# uNav44_r1.net
KiCad netlist of a schematic drawn in EAGLE
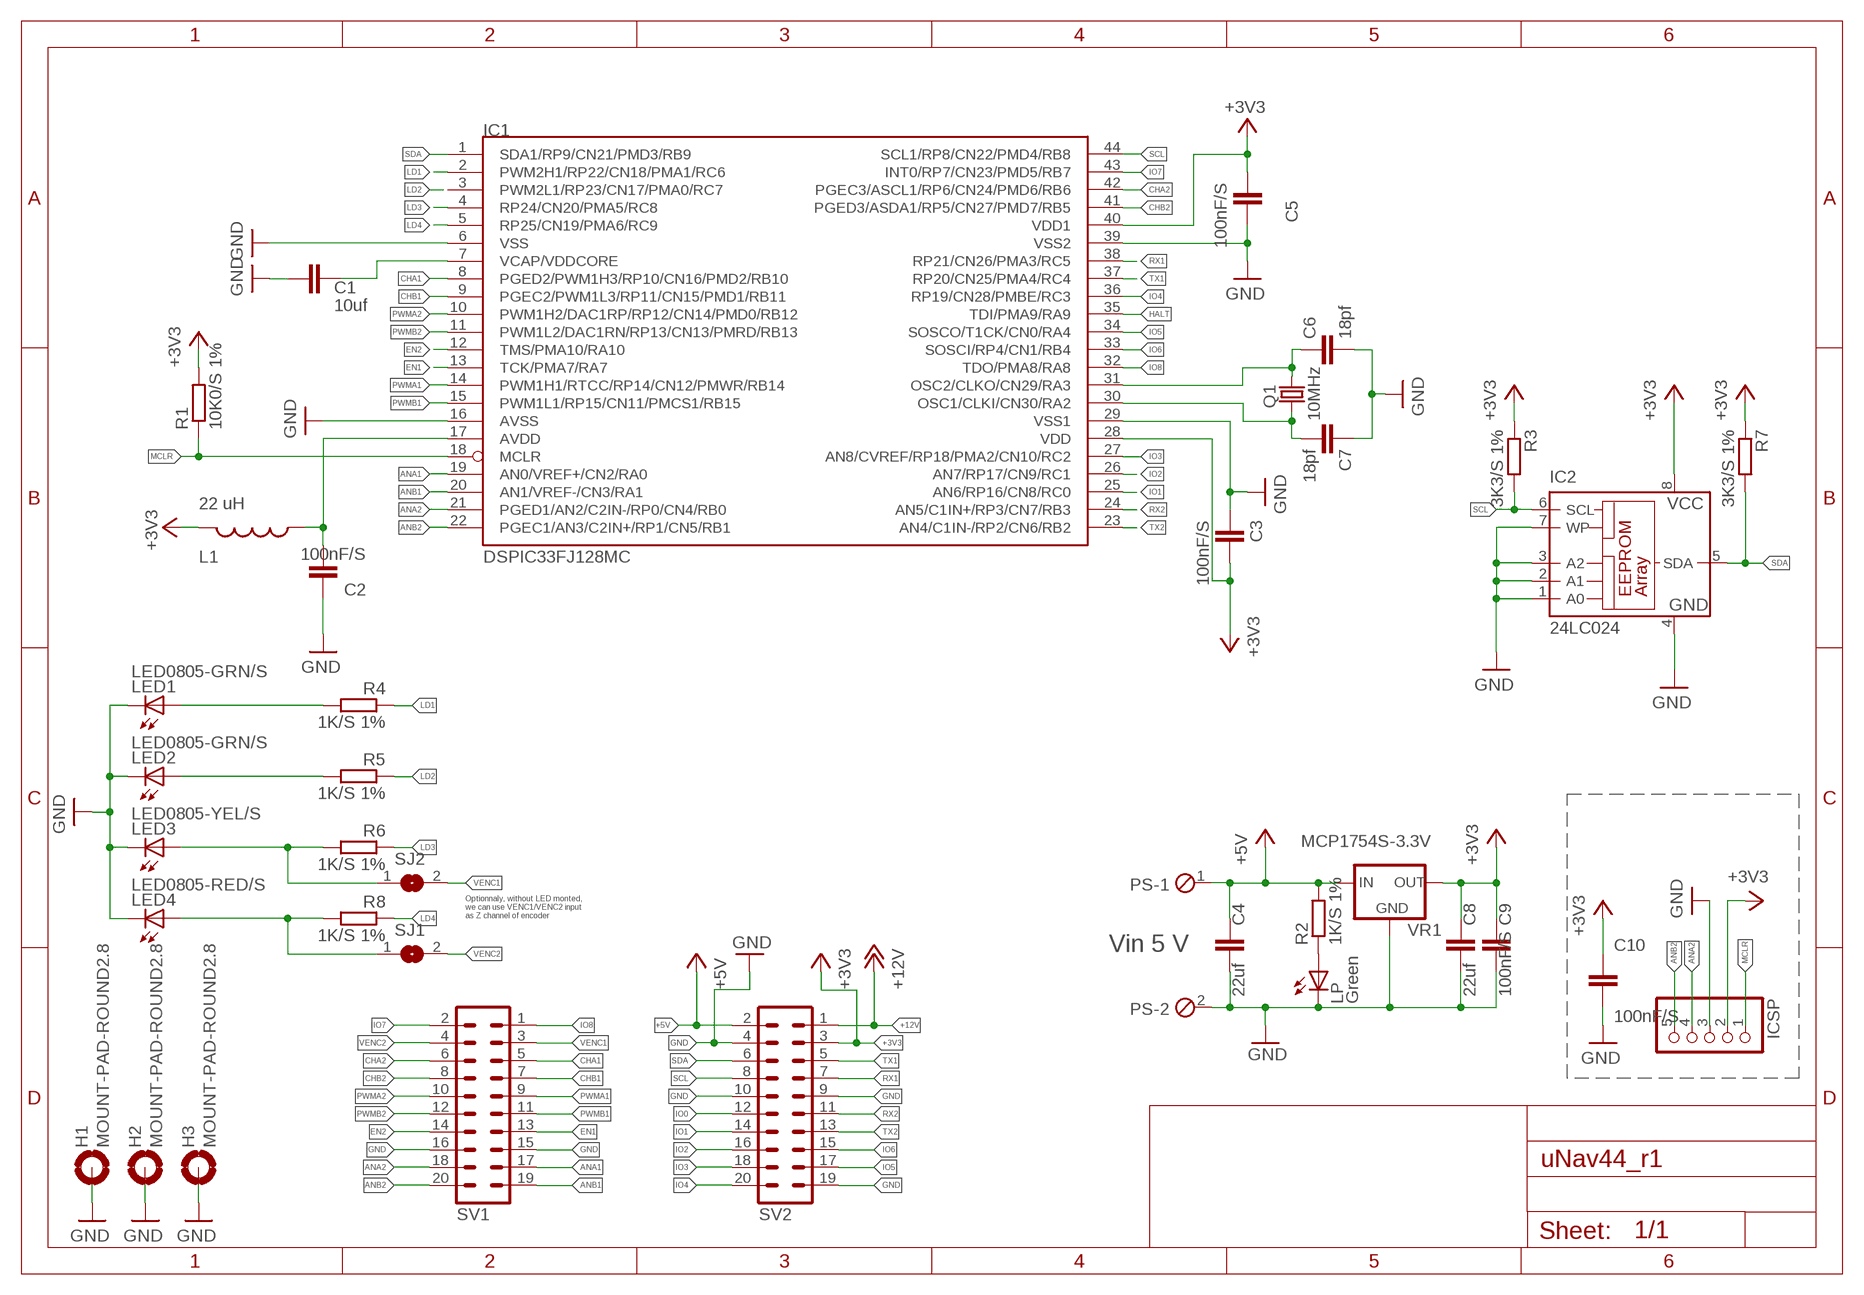
[diagram p0: schematic, sheet 1]

(export (version "E")
  (design (tool "Eeschema 10.0.6"))
  (components
    (comp (ref "C1")
      (value "10uf")
      (footprint "eagle-import:C1206")
      (libsource (lib "eagle-import") (part "C-EUC1206"))
    )
    (comp (ref "C2")
      (value "100nF/S")
      (footprint "eagle-import:C0603")
      (libsource (lib "eagle-import") (part "C-EUC0603"))
    )
    (comp (ref "C3")
      (value "100nF/S")
      (footprint "eagle-import:C0603")
      (libsource (lib "eagle-import") (part "C-EUC0603"))
    )
    (comp (ref "C4")
      (value "22uf")
      (footprint "eagle-import:C1206")
      (libsource (lib "eagle-import") (part "C-EUC1206"))
    )
    (comp (ref "C5")
      (value "100nF/S")
      (footprint "eagle-import:C0603")
      (libsource (lib "eagle-import") (part "C-EUC0603"))
    )
    (comp (ref "C6")
      (value "18pf")
      (footprint "eagle-import:C0603")
      (libsource (lib "eagle-import") (part "C-EUC0603"))
    )
    (comp (ref "C7")
      (value "18pf")
      (footprint "eagle-import:C0603")
      (libsource (lib "eagle-import") (part "C-EUC0603"))
    )
    (comp (ref "C8")
      (value "22uf")
      (footprint "eagle-import:C1206")
      (libsource (lib "eagle-import") (part "C-EUC1206"))
    )
    (comp (ref "C9")
      (value "100nF/S")
      (footprint "eagle-import:C0603")
      (libsource (lib "eagle-import") (part "C-EUC0603"))
    )
    (comp (ref "C10")
      (value "100nF/S")
      (footprint "eagle-import:C0603")
      (libsource (lib "eagle-import") (part "C-EUC0603"))
    )
    (comp (ref "H1")
      (value "MOUNT-PAD-ROUND2.8")
      (footprint "eagle-import:2,8-PAD")
      (libsource (lib "eagle-import") (part "MOUNT-PAD-ROUND2.8"))
    )
    (comp (ref "H2")
      (value "MOUNT-PAD-ROUND2.8")
      (footprint "eagle-import:2,8-PAD")
      (libsource (lib "eagle-import") (part "MOUNT-PAD-ROUND2.8"))
    )
    (comp (ref "H3")
      (value "MOUNT-PAD-ROUND2.8")
      (footprint "eagle-import:2,8-PAD")
      (libsource (lib "eagle-import") (part "MOUNT-PAD-ROUND2.8"))
    )
    (comp (ref "IC1")
      (value "DSPIC33FJ128MC")
      (footprint "eagle-import:TQFP44")
      (libsource (lib "eagle-import") (part "DSPIC33FJ128MC804-PT"))
    )
    (comp (ref "IC2")
      (value "24LC024")
      (footprint "eagle-import:SO-08M")
      (fields (field (name "MF") "MICROCHIP") (field (name "MPN") "24AA01-I/SN"))
      (libsource (lib "eagle-import") (part "24SMAA01"))
    )
    (comp (ref "ICSP")
      (value "PINHD-1X05_2.54-S")
      (footprint "eagle-import:1X05-S")
      (libsource (lib "eagle-import") (part "PINHD-1X05_2.54-S"))
    )
    (comp (ref "L1")
      (value "22 uH")
      (footprint "eagle-import:0805")
      (libsource (lib "eagle-import") (part "INDUCTOR0805"))
    )
    (comp (ref "LED1")
      (value "LED0805-GRN/S")
      (footprint "eagle-import:CHIPLED_0805")
      (libsource (lib "eagle-import") (part "LEDCHIPLED_0805"))
    )
    (comp (ref "LED2")
      (value "LED0805-GRN/S")
      (footprint "eagle-import:CHIPLED_0805")
      (libsource (lib "eagle-import") (part "LEDCHIPLED_0805"))
    )
    (comp (ref "LED3")
      (value "LED0805-YEL/S")
      (footprint "eagle-import:CHIPLED_0805")
      (libsource (lib "eagle-import") (part "LEDCHIPLED_0805"))
    )
    (comp (ref "LED4")
      (value "LED0805-RED/S")
      (footprint "eagle-import:CHIPLED_0805")
      (libsource (lib "eagle-import") (part "LEDCHIPLED_0805"))
    )
    (comp (ref "LP")
      (value "Green")
      (footprint "eagle-import:CHIPLED_0805")
      (libsource (lib "eagle-import") (part "LEDCHIPLED_0805"))
    )
    (comp (ref "PS")
      (value "MPT2")
      (footprint "eagle-import:2POL254")
      (libsource (lib "eagle-import") (part "MPT2"))
    )
    (comp (ref "Q1")
      (value "10MHz")
      (footprint "eagle-import:HC49U-V")
      (libsource (lib "eagle-import") (part "CRYSTALHC49U-V"))
    )
    (comp (ref "R1")
      (value "10K0/S 1%")
      (footprint "eagle-import:R0603")
      (libsource (lib "eagle-import") (part "R-EU_R0603"))
    )
    (comp (ref "R2")
      (value "1K/S 1%")
      (footprint "eagle-import:R0603")
      (libsource (lib "eagle-import") (part "R-EU_R0603"))
    )
    (comp (ref "R3")
      (value "3K3/S 1%")
      (footprint "eagle-import:R0603")
      (libsource (lib "eagle-import") (part "R-EU_R0603"))
    )
    (comp (ref "R4")
      (value "1K/S 1%")
      (footprint "eagle-import:R0603")
      (libsource (lib "eagle-import") (part "R-EU_R0603"))
    )
    (comp (ref "R5")
      (value "1K/S 1%")
      (footprint "eagle-import:R0603")
      (libsource (lib "eagle-import") (part "R-EU_R0603"))
    )
    (comp (ref "R6")
      (value "1K/S 1%")
      (footprint "eagle-import:R0603")
      (libsource (lib "eagle-import") (part "R-EU_R0603"))
    )
    (comp (ref "R7")
      (value "3K3/S 1%")
      (footprint "eagle-import:R0603")
      (libsource (lib "eagle-import") (part "R-EU_R0603"))
    )
    (comp (ref "R8")
      (value "1K/S 1%")
      (footprint "eagle-import:R0603")
      (libsource (lib "eagle-import") (part "R-EU_R0603"))
    )
    (comp (ref "SJ1") (value "SJ") (footprint "eagle-import:SJ") (libsource (lib "eagle-import") (part "SJ")))
    (comp (ref "SJ2") (value "SJ") (footprint "eagle-import:SJ") (libsource (lib "eagle-import") (part "SJ")))
    (comp (ref "SV1")
      (value "MA10-2")
      (footprint "eagle-import:MA10-2")
      (fields (field (name "OC_FARNELL") "unknown") (field (name "OC_NEWARK") "unknown"))
      (libsource (lib "eagle-import") (part "MA10-2"))
    )
    (comp (ref "SV2")
      (value "MA10-2")
      (footprint "eagle-import:MA10-2")
      (libsource (lib "eagle-import") (part "MA10-2"))
    )
    (comp (ref "VR1")
      (value "MCP1754S-3.3V")
      (footprint "eagle-import:SOT89")
      (libsource (lib "eagle-import") (part "MCP1754S"))
    )
  )
  (nets
    (net (code "1") (name "+3V3") (class "Default")
      (node (ref "C10") (pin "1") (pinfunction "1_1") (pintype "passive"))
      (node (ref "C3") (pin "1") (pinfunction "1_1") (pintype "passive"))
      (node (ref "C5") (pin "2") (pinfunction "2_2") (pintype "passive"))
      (node (ref "C8") (pin "1") (pinfunction "1_1") (pintype "passive"))
      (node (ref "C9") (pin "1") (pinfunction "1_1") (pintype "passive"))
      (node (ref "IC1") (pin "28") (pinfunction "VDD_28") (pintype "power_in"))
      (node (ref "IC1") (pin "40") (pinfunction "VDD1_40") (pintype "power_in"))
      (node (ref "IC2") (pin "8") (pinfunction "VCC_8") (pintype "power_in"))
      (node (ref "ICSP") (pin "2") (pinfunction "2_2") (pintype "passive"))
      (node (ref "L1") (pin "2") (pinfunction "2_2") (pintype "passive"))
      (node (ref "R1") (pin "2") (pinfunction "2_2") (pintype "passive"))
      (node (ref "R3") (pin "1") (pinfunction "1_1") (pintype "passive"))
      (node (ref "R7") (pin "1") (pinfunction "1_1") (pintype "passive"))
      (node (ref "SV2") (pin "3") (pinfunction "3_3") (pintype "passive"))
      (node (ref "VR1") (pin "3") (pinfunction "OUT_3") (pintype "passive"))
    )
    (net (code "2") (name "+5V") (class "Default")
      (node (ref "C4") (pin "1") (pinfunction "1_1") (pintype "passive"))
      (node (ref "PS") (pin "1") (pinfunction "1_1") (pintype "passive"))
      (node (ref "R2") (pin "2") (pinfunction "2_2") (pintype "passive"))
      (node (ref "SV2") (pin "2") (pinfunction "2_2") (pintype "passive"))
      (node (ref "VR1") (pin "1") (pinfunction "IN_1") (pintype "input"))
    )
    (net (code "3") (name "+12V") (class "Default")
      (node (ref "SV2") (pin "1") (pinfunction "1_1") (pintype "passive"))
    )
    (net (code "4") (name "ANA1") (class "Default")
      (node (ref "IC1") (pin "19") (pinfunction "AN0/VREF+/CN2/RA0_19") (pintype "bidirectional"))
      (node (ref "SV1") (pin "17") (pinfunction "17_17") (pintype "passive"))
    )
    (net (code "5") (name "ANA2") (class "Default")
      (node (ref "IC1") (pin "21") (pinfunction "PGED1/AN2/C2IN-/RP0/CN4/RB0_21") (pintype "bidirectional"))
      (node (ref "ICSP") (pin "4") (pinfunction "4_4") (pintype "passive"))
      (node (ref "SV1") (pin "18") (pinfunction "18_18") (pintype "passive"))
    )
    (net (code "6") (name "ANB1") (class "Default")
      (node (ref "IC1") (pin "20") (pinfunction "AN1/VREF-/CN3/RA1_20") (pintype "bidirectional"))
      (node (ref "SV1") (pin "19") (pinfunction "19_19") (pintype "passive"))
    )
    (net (code "7") (name "ANB2") (class "Default")
      (node (ref "IC1") (pin "22") (pinfunction "PGEC1/AN3/C2IN+/RP1/CN5/RB1_22") (pintype "bidirectional"))
      (node (ref "ICSP") (pin "5") (pinfunction "5_5") (pintype "passive"))
      (node (ref "SV1") (pin "20") (pinfunction "20_20") (pintype "passive"))
    )
    (net (code "8") (name "CHA1") (class "Default")
      (node (ref "IC1") (pin "8") (pinfunction "PGED2/PWM1H3/RP10/CN16/PMD2/RB10_8") (pintype "bidirectional"))
      (node (ref "SV1") (pin "5") (pinfunction "5_5") (pintype "passive"))
    )
    (net (code "9") (name "CHA2") (class "Default")
      (node (ref "IC1") (pin "42") (pinfunction "PGEC3/ASCL1/RP6/CN24/PMD6/RB6_42") (pintype "bidirectional"))
      (node (ref "SV1") (pin "6") (pinfunction "6_6") (pintype "passive"))
    )
    (net (code "10") (name "CHB1") (class "Default")
      (node (ref "IC1") (pin "9") (pinfunction "PGEC2/PWM1L3/RP11/CN15/PMD1/RB11_9") (pintype "bidirectional"))
      (node (ref "SV1") (pin "7") (pinfunction "7_7") (pintype "passive"))
    )
    (net (code "11") (name "CHB2") (class "Default")
      (node (ref "IC1") (pin "41") (pinfunction "PGED3/ASDA1/RP5/CN27/PMD7/RB5_41") (pintype "bidirectional"))
      (node (ref "SV1") (pin "8") (pinfunction "8_8") (pintype "passive"))
    )
    (net (code "12") (name "EN1") (class "Default")
      (node (ref "IC1") (pin "13") (pinfunction "TCK/PMA7/RA7_13") (pintype "bidirectional"))
      (node (ref "SV1") (pin "13") (pinfunction "13_13") (pintype "passive"))
    )
    (net (code "13") (name "EN2") (class "Default")
      (node (ref "IC1") (pin "12") (pinfunction "TMS/PMA10/RA10_12") (pintype "bidirectional"))
      (node (ref "SV1") (pin "14") (pinfunction "14_14") (pintype "passive"))
    )
    (net (code "14") (name "GND") (class "Default")
      (node (ref "C1") (pin "2") (pinfunction "2_2") (pintype "passive"))
      (node (ref "C10") (pin "2") (pinfunction "2_2") (pintype "passive"))
      (node (ref "C2") (pin "1") (pinfunction "1_1") (pintype "passive"))
      (node (ref "C3") (pin "2") (pinfunction "2_2") (pintype "passive"))
      (node (ref "C4") (pin "2") (pinfunction "2_2") (pintype "passive"))
      (node (ref "C5") (pin "1") (pinfunction "1_1") (pintype "passive"))
      (node (ref "C6") (pin "2") (pinfunction "2_2") (pintype "passive"))
      (node (ref "C7") (pin "1") (pinfunction "1_1") (pintype "passive"))
      (node (ref "C8") (pin "2") (pinfunction "2_2") (pintype "passive"))
      (node (ref "C9") (pin "2") (pinfunction "2_2") (pintype "passive"))
      (node (ref "H1") (pin "B2,8") (pinfunction "MOUNT_B2,8") (pintype "passive"))
      (node (ref "H2") (pin "B2,8") (pinfunction "MOUNT_B2,8") (pintype "passive"))
      (node (ref "H3") (pin "B2,8") (pinfunction "MOUNT_B2,8") (pintype "passive"))
      (node (ref "IC1") (pin "16") (pinfunction "AVSS_16") (pintype "power_in"))
      (node (ref "IC1") (pin "29") (pinfunction "VSS1_29") (pintype "power_in"))
      (node (ref "IC1") (pin "39") (pinfunction "VSS2_39") (pintype "power_in"))
      (node (ref "IC1") (pin "6") (pinfunction "VSS_6") (pintype "power_in"))
      (node (ref "IC2") (pin "1") (pinfunction "A0_1") (pintype "input"))
      (node (ref "IC2") (pin "2") (pinfunction "A1_2") (pintype "input"))
      (node (ref "IC2") (pin "3") (pinfunction "A2_3") (pintype "input"))
      (node (ref "IC2") (pin "4") (pinfunction "GND_4") (pintype "power_in"))
      (node (ref "IC2") (pin "7") (pinfunction "WP_7") (pintype "input"))
      (node (ref "ICSP") (pin "3") (pinfunction "3_3") (pintype "passive"))
      (node (ref "LED1") (pin "C") (pinfunction "C_C") (pintype "passive"))
      (node (ref "LED2") (pin "C") (pinfunction "C_C") (pintype "passive"))
      (node (ref "LED3") (pin "C") (pinfunction "C_C") (pintype "passive"))
      (node (ref "LED4") (pin "C") (pinfunction "C_C") (pintype "passive"))
      (node (ref "LP") (pin "C") (pinfunction "C_C") (pintype "passive"))
      (node (ref "PS") (pin "2") (pinfunction "1_2") (pintype "passive"))
      (node (ref "SV1") (pin "15") (pinfunction "15_15") (pintype "passive"))
      (node (ref "SV1") (pin "16") (pinfunction "16_16") (pintype "passive"))
      (node (ref "SV2") (pin "10") (pinfunction "10_10") (pintype "passive"))
      (node (ref "SV2") (pin "19") (pinfunction "19_19") (pintype "passive"))
      (node (ref "SV2") (pin "4") (pinfunction "4_4") (pintype "passive"))
      (node (ref "SV2") (pin "9") (pinfunction "9_9") (pintype "passive"))
      (node (ref "VR1") (pin "2") (pinfunction "GND_2") (pintype "input"))
      (node (ref "VR1") (pin "4") (pinfunction "GND_4") (pintype "input"))
    )
    (net (code "15") (name "HALT") (class "Default")
      (node (ref "IC1") (pin "35") (pinfunction "TDI/PMA9/RA9_35") (pintype "bidirectional"))
    )
    (net (code "16") (name "IO0") (class "Default")
      (node (ref "SV2") (pin "12") (pinfunction "12_12") (pintype "passive"))
    )
    (net (code "17") (name "IO1") (class "Default")
      (node (ref "IC1") (pin "25") (pinfunction "AN6/RP16/CN8/RC0_25") (pintype "bidirectional"))
      (node (ref "SV2") (pin "14") (pinfunction "14_14") (pintype "passive"))
    )
    (net (code "18") (name "IO2") (class "Default")
      (node (ref "IC1") (pin "26") (pinfunction "AN7/RP17/CN9/RC1_26") (pintype "bidirectional"))
      (node (ref "SV2") (pin "16") (pinfunction "16_16") (pintype "passive"))
    )
    (net (code "19") (name "IO3") (class "Default")
      (node (ref "IC1") (pin "27") (pinfunction "AN8/CVREF/RP18/PMA2/CN10/RC2_27") (pintype "bidirectional"))
      (node (ref "SV2") (pin "18") (pinfunction "18_18") (pintype "passive"))
    )
    (net (code "20") (name "IO4") (class "Default")
      (node (ref "IC1") (pin "36") (pinfunction "RP19/CN28/PMBE/RC3_36") (pintype "bidirectional"))
      (node (ref "SV2") (pin "20") (pinfunction "20_20") (pintype "passive"))
    )
    (net (code "21") (name "IO5") (class "Default")
      (node (ref "IC1") (pin "34") (pinfunction "SOSCO/T1CK/CN0/RA4_34") (pintype "bidirectional"))
      (node (ref "SV2") (pin "17") (pinfunction "17_17") (pintype "passive"))
    )
    (net (code "22") (name "IO6") (class "Default")
      (node (ref "IC1") (pin "33") (pinfunction "SOSCI/RP4/CN1/RB4_33") (pintype "bidirectional"))
      (node (ref "SV2") (pin "15") (pinfunction "15_15") (pintype "passive"))
    )
    (net (code "23") (name "IO7") (class "Default")
      (node (ref "IC1") (pin "43") (pinfunction "INT0/RP7/CN23/PMD5/RB7_43") (pintype "bidirectional"))
      (node (ref "SV1") (pin "2") (pinfunction "2_2") (pintype "passive"))
    )
    (net (code "24") (name "IO8") (class "Default")
      (node (ref "IC1") (pin "32") (pinfunction "TDO/PMA8/RA8_32") (pintype "bidirectional"))
      (node (ref "SV1") (pin "1") (pinfunction "1_1") (pintype "passive"))
    )
    (net (code "25") (name "LD1") (class "Default")
      (node (ref "IC1") (pin "2") (pinfunction "PWM2H1/RP22/CN18/PMA1/RC6_2") (pintype "bidirectional"))
      (node (ref "R4") (pin "1") (pinfunction "1_1") (pintype "passive"))
    )
    (net (code "26") (name "LD2") (class "Default")
      (node (ref "IC1") (pin "3") (pinfunction "PWM2L1/RP23/CN17/PMA0/RC7_3") (pintype "bidirectional"))
      (node (ref "R5") (pin "1") (pinfunction "1_1") (pintype "passive"))
    )
    (net (code "27") (name "LD3") (class "Default")
      (node (ref "IC1") (pin "4") (pinfunction "RP24/CN20/PMA5/RC8_4") (pintype "bidirectional"))
      (node (ref "R6") (pin "1") (pinfunction "1_1") (pintype "passive"))
    )
    (net (code "28") (name "LD4") (class "Default")
      (node (ref "IC1") (pin "5") (pinfunction "RP25/CN19/PMA6/RC9_5") (pintype "bidirectional"))
      (node (ref "R8") (pin "1") (pinfunction "1_1") (pintype "passive"))
    )
    (net (code "29") (name "MCLR") (class "Default")
      (node (ref "IC1") (pin "18") (pinfunction "MCLR_18") (pintype "input"))
      (node (ref "ICSP") (pin "1") (pinfunction "1_1") (pintype "passive"))
      (node (ref "R1") (pin "1") (pinfunction "1_1") (pintype "passive"))
    )
    (net (code "30") (name "Net-(IC1-AVDD)") (class "Default")
      (node (ref "C2") (pin "2") (pinfunction "2_2") (pintype "passive"))
      (node (ref "IC1") (pin "17") (pinfunction "AVDD_17") (pintype "power_in"))
      (node (ref "L1") (pin "1") (pinfunction "1_1") (pintype "passive"))
    )
    (net (code "31") (name "Net-(IC1-OSC1{slash}CLKI{slash}CN30{slash}RA2)") (class "Default")
      (node (ref "C7") (pin "2") (pinfunction "2_2") (pintype "passive"))
      (node (ref "IC1") (pin "30") (pinfunction "OSC1/CLKI/CN30/RA2_30") (pintype "bidirectional"))
      (node (ref "Q1") (pin "1") (pinfunction "1_1") (pintype "passive"))
    )
    (net (code "32") (name "Net-(IC1-OSC2{slash}CLKO{slash}CN29{slash}RA3)") (class "Default")
      (node (ref "C6") (pin "1") (pinfunction "1_1") (pintype "passive"))
      (node (ref "IC1") (pin "31") (pinfunction "OSC2/CLKO/CN29/RA3_31") (pintype "bidirectional"))
      (node (ref "Q1") (pin "2") (pinfunction "2_2") (pintype "passive"))
    )
    (net (code "33") (name "Net-(IC1-VCAP{slash}VDDCORE)") (class "Default")
      (node (ref "C1") (pin "1") (pinfunction "1_1") (pintype "passive"))
      (node (ref "IC1") (pin "7") (pinfunction "VCAP/VDDCORE_7") (pintype "power_in"))
    )
    (net (code "34") (name "Net-(LED1-PadA)") (class "Default")
      (node (ref "LED1") (pin "A") (pinfunction "A_A") (pintype "passive"))
      (node (ref "R4") (pin "2") (pinfunction "2_2") (pintype "passive"))
    )
    (net (code "35") (name "Net-(LED2-PadA)") (class "Default")
      (node (ref "LED2") (pin "A") (pinfunction "A_A") (pintype "passive"))
      (node (ref "R5") (pin "2") (pinfunction "2_2") (pintype "passive"))
    )
    (net (code "36") (name "Net-(LED3-PadA)") (class "Default")
      (node (ref "LED3") (pin "A") (pinfunction "A_A") (pintype "passive"))
      (node (ref "R6") (pin "2") (pinfunction "2_2") (pintype "passive"))
      (node (ref "SJ2") (pin "1") (pinfunction "1_1") (pintype "passive"))
    )
    (net (code "37") (name "Net-(LED4-PadA)") (class "Default")
      (node (ref "LED4") (pin "A") (pinfunction "A_A") (pintype "passive"))
      (node (ref "R8") (pin "2") (pinfunction "2_2") (pintype "passive"))
      (node (ref "SJ1") (pin "1") (pinfunction "1_1") (pintype "passive"))
    )
    (net (code "38") (name "Net-(LP-PadA)") (class "Default")
      (node (ref "LP") (pin "A") (pinfunction "A_A") (pintype "passive"))
      (node (ref "R2") (pin "1") (pinfunction "1_1") (pintype "passive"))
    )
    (net (code "39") (name "PWMA1") (class "Default")
      (node (ref "IC1") (pin "14") (pinfunction "PWM1H1/RTCC/RP14/CN12/PMWR/RB14_14") (pintype "bidirectional"))
      (node (ref "SV1") (pin "9") (pinfunction "9_9") (pintype "passive"))
    )
    (net (code "40") (name "PWMA2") (class "Default")
      (node (ref "IC1") (pin "10") (pinfunction "PWM1H2/DAC1RP/RP12/CN14/PMD0/RB12_10") (pintype "bidirectional"))
      (node (ref "SV1") (pin "10") (pinfunction "10_10") (pintype "passive"))
    )
    (net (code "41") (name "PWMB1") (class "Default")
      (node (ref "IC1") (pin "15") (pinfunction "PWM1L1/RP15/CN11/PMCS1/RB15_15") (pintype "bidirectional"))
      (node (ref "SV1") (pin "11") (pinfunction "11_11") (pintype "passive"))
    )
    (net (code "42") (name "PWMB2") (class "Default")
      (node (ref "IC1") (pin "11") (pinfunction "PWM1L2/DAC1RN/RP13/CN13/PMRD/RB13_11") (pintype "bidirectional"))
      (node (ref "SV1") (pin "12") (pinfunction "12_12") (pintype "passive"))
    )
    (net (code "43") (name "RX1") (class "Default")
      (node (ref "IC1") (pin "38") (pinfunction "RP21/CN26/PMA3/RC5_38") (pintype "bidirectional"))
      (node (ref "SV2") (pin "7") (pinfunction "7_7") (pintype "passive"))
    )
    (net (code "44") (name "RX2") (class "Default")
      (node (ref "IC1") (pin "24") (pinfunction "AN5/C1IN+/RP3/CN7/RB3_24") (pintype "bidirectional"))
      (node (ref "SV2") (pin "11") (pinfunction "11_11") (pintype "passive"))
    )
    (net (code "45") (name "SCL") (class "Default")
      (node (ref "IC1") (pin "44") (pinfunction "SCL1/RP8/CN22/PMD4/RB8_44") (pintype "bidirectional"))
      (node (ref "IC2") (pin "6") (pinfunction "SCL_6") (pintype "input"))
      (node (ref "R3") (pin "2") (pinfunction "2_2") (pintype "passive"))
      (node (ref "SV2") (pin "8") (pinfunction "8_8") (pintype "passive"))
    )
    (net (code "46") (name "SDA") (class "Default")
      (node (ref "IC1") (pin "1") (pinfunction "SDA1/RP9/CN21/PMD3/RB9_1") (pintype "bidirectional"))
      (node (ref "IC2") (pin "5") (pinfunction "SDA_5") (pintype "bidirectional"))
      (node (ref "R7") (pin "2") (pinfunction "2_2") (pintype "passive"))
      (node (ref "SV2") (pin "6") (pinfunction "6_6") (pintype "passive"))
    )
    (net (code "47") (name "TX1") (class "Default")
      (node (ref "IC1") (pin "37") (pinfunction "RP20/CN25/PMA4/RC4_37") (pintype "bidirectional"))
      (node (ref "SV2") (pin "5") (pinfunction "5_5") (pintype "passive"))
    )
    (net (code "48") (name "TX2") (class "Default")
      (node (ref "IC1") (pin "23") (pinfunction "AN4/C1IN-/RP2/CN6/RB2_23") (pintype "bidirectional"))
      (node (ref "SV2") (pin "13") (pinfunction "13_13") (pintype "passive"))
    )
    (net (code "49") (name "VENC1") (class "Default")
      (node (ref "SJ2") (pin "2") (pinfunction "2_2") (pintype "passive"))
      (node (ref "SV1") (pin "3") (pinfunction "3_3") (pintype "passive"))
    )
    (net (code "50") (name "VENC2") (class "Default")
      (node (ref "SJ1") (pin "2") (pinfunction "2_2") (pintype "passive"))
      (node (ref "SV1") (pin "4") (pinfunction "4_4") (pintype "passive"))
    )
  )
)
